# astabilny_generator_sygnalu.net
KiCad netlist of a schematic drawn in Altium Designer
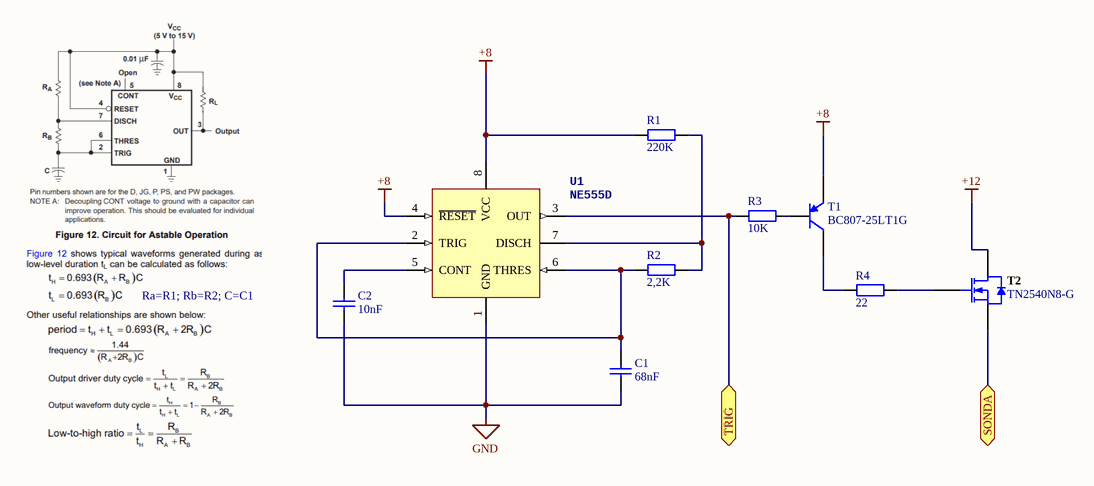
[diagram p0: astabilny generator sygnalu.SchDoc]

(export (version "E")
  (design (tool "Eeschema 10.0.6"))
  (components
    (comp (ref "C1")
      (value "C0603C683K5RACTU@TME")
      (footprint "0603")
      (description "Capacitor")
      (fields (field (name "CAPACITANCE") "68nF"))
      (libsource (lib "MT_Library") (part "Cap"))
    )
    (comp (ref "C2")
      (value "CL10B103KB8NNNC@TME")
      (footprint "0603")
      (description "Capacitor")
      (fields (field (name "CAPACITANCE") "10nF"))
      (libsource (lib "MT_Library") (part "Cap"))
    )
    (comp (ref "R1")
      (value "220K")
      (footprint "R1206")
      (description "Resistor")
      (fields (field (name "Comment") "1206S4J0224T5E@TME"))
      (libsource (lib "MT_Library") (part "Res"))
    )
    (comp (ref "R2")
      (value "2,2K")
      (footprint "R1206")
      (description "Resistor")
      (fields (field (name "Comment") "1206S4J0222T5E@TME"))
      (libsource (lib "MT_Library") (part "Res"))
    )
    (comp (ref "R3")
      (value "10K")
      (footprint "R1206")
      (description "Resistor")
      (fields (field (name "Comment") "1206S4J0103T5E@TME"))
      (libsource (lib "MT_Library") (part "Res"))
    )
    (comp (ref "R4")
      (value "22")
      (footprint "R1206")
      (description "Resistor")
      (fields (field (name "Comment") "1206S4J0220T5E@TME"))
      (libsource (lib "MT_Library") (part "Res"))
    )
    (comp (ref "T1")
      (value "BC807-25LT1G")
      (footprint "ONSC-SOT-23-3-318-08_V")
      (description "General Purpose Transistor, PNP Silicon, 3-Pin SOT-23, Pb-Free, Tape and Reel")
      (fields (field (name "MANUFACTURER") "On Semiconductor"))
      (libsource (lib "Altium Content Vault") (part "ONSC-PNP-B1E2C3-3"))
    )
    (comp (ref "T2")
      (value "TN2540N8-G")
      (footprint "MCHP-TO-243AA_N8_L")
      (fields (field (name "MANUFACTURER") "Microchip"))
      (libsource (lib "Altium Content Vault") (part "NEMOS-GDS-3"))
    )
    (comp (ref "U1")
      (value "NE555D")
      (footprint "D0008A_L")
      (description "Precision Timer, 4.5 to 16 V, 0 to 70 degC, 8-Pin SOIC (D), Green (RoHS & no Sb/Br), Tube")
      (fields (field (name "PARTNUMBER") "NE555") (field (name "MANUFACTURER") "Texas Instruments"))
      (libsource (lib "MetalDetLibrary") (part "NE555"))
    )
  )
  (nets
    (net (code "1") (name "+8") (class "Default")
      (node (ref "R1") (pin "1") (pinfunction "1_1") (pintype "passive"))
      (node (ref "T1") (pin "2") (pinfunction "E_2") (pintype "passive"))
      (node (ref "U1") (pin "4") (pinfunction "~{RESET}_4") (pintype "input"))
      (node (ref "U1") (pin "8") (pinfunction "VCC_8") (pintype "power_in"))
    )
    (net (code "2") (name "+12") (class "Default")
      (node (ref "T2") (pin "2") (pinfunction "D_2") (pintype "passive"))
    )
    (net (code "3") (name "/SONDA") (class "Default")
      (node (ref "T2") (pin "3") (pinfunction "S_3") (pintype "passive"))
    )
    (net (code "4") (name "/TRIG") (class "Default")
      (node (ref "R3") (pin "1") (pinfunction "1_1") (pintype "passive"))
      (node (ref "U1") (pin "3") (pinfunction "OUT_3") (pintype "output"))
    )
    (net (code "5") (name "GND") (class "Default")
      (node (ref "C1") (pin "2") (pinfunction "2_2") (pintype "passive"))
      (node (ref "C2") (pin "2") (pinfunction "2_2") (pintype "passive"))
      (node (ref "U1") (pin "1") (pinfunction "GND_1") (pintype "power_in"))
    )
    (net (code "6") (name "Net-(T1-B)") (class "Default")
      (node (ref "R3") (pin "2") (pinfunction "2_2") (pintype "passive"))
      (node (ref "T1") (pin "1") (pinfunction "B_1") (pintype "passive"))
    )
    (net (code "7") (name "Net-(T1-C)") (class "Default")
      (node (ref "R4") (pin "1") (pinfunction "1_1") (pintype "passive"))
      (node (ref "T1") (pin "3") (pinfunction "C_3") (pintype "passive"))
    )
    (net (code "8") (name "Net-(T2-G)") (class "Default")
      (node (ref "R4") (pin "2") (pinfunction "2_2") (pintype "passive"))
      (node (ref "T2") (pin "1") (pinfunction "G_1") (pintype "passive"))
    )
    (net (code "9") (name "Net-(U1-CONT)") (class "Default")
      (node (ref "C2") (pin "1") (pinfunction "1_1") (pintype "passive"))
      (node (ref "U1") (pin "5") (pinfunction "CONT_5") (pintype "input"))
    )
    (net (code "10") (name "Net-(U1-DISCH)") (class "Default")
      (node (ref "R1") (pin "2") (pinfunction "2_2") (pintype "passive"))
      (node (ref "R2") (pin "2") (pinfunction "2_2") (pintype "passive"))
      (node (ref "U1") (pin "7") (pinfunction "DISCH_7") (pintype "open_collector"))
    )
    (net (code "11") (name "Net-(U1-THRES)") (class "Default")
      (node (ref "C1") (pin "1") (pinfunction "1_1") (pintype "passive"))
      (node (ref "R2") (pin "1") (pinfunction "1_1") (pintype "passive"))
      (node (ref "U1") (pin "2") (pinfunction "TRIG_2") (pintype "input"))
      (node (ref "U1") (pin "6") (pinfunction "THRES_6") (pintype "input"))
    )
  )
)
